# STM32_microcontroller_RF.net
KiCad netlist of a schematic drawn in Altium Designer
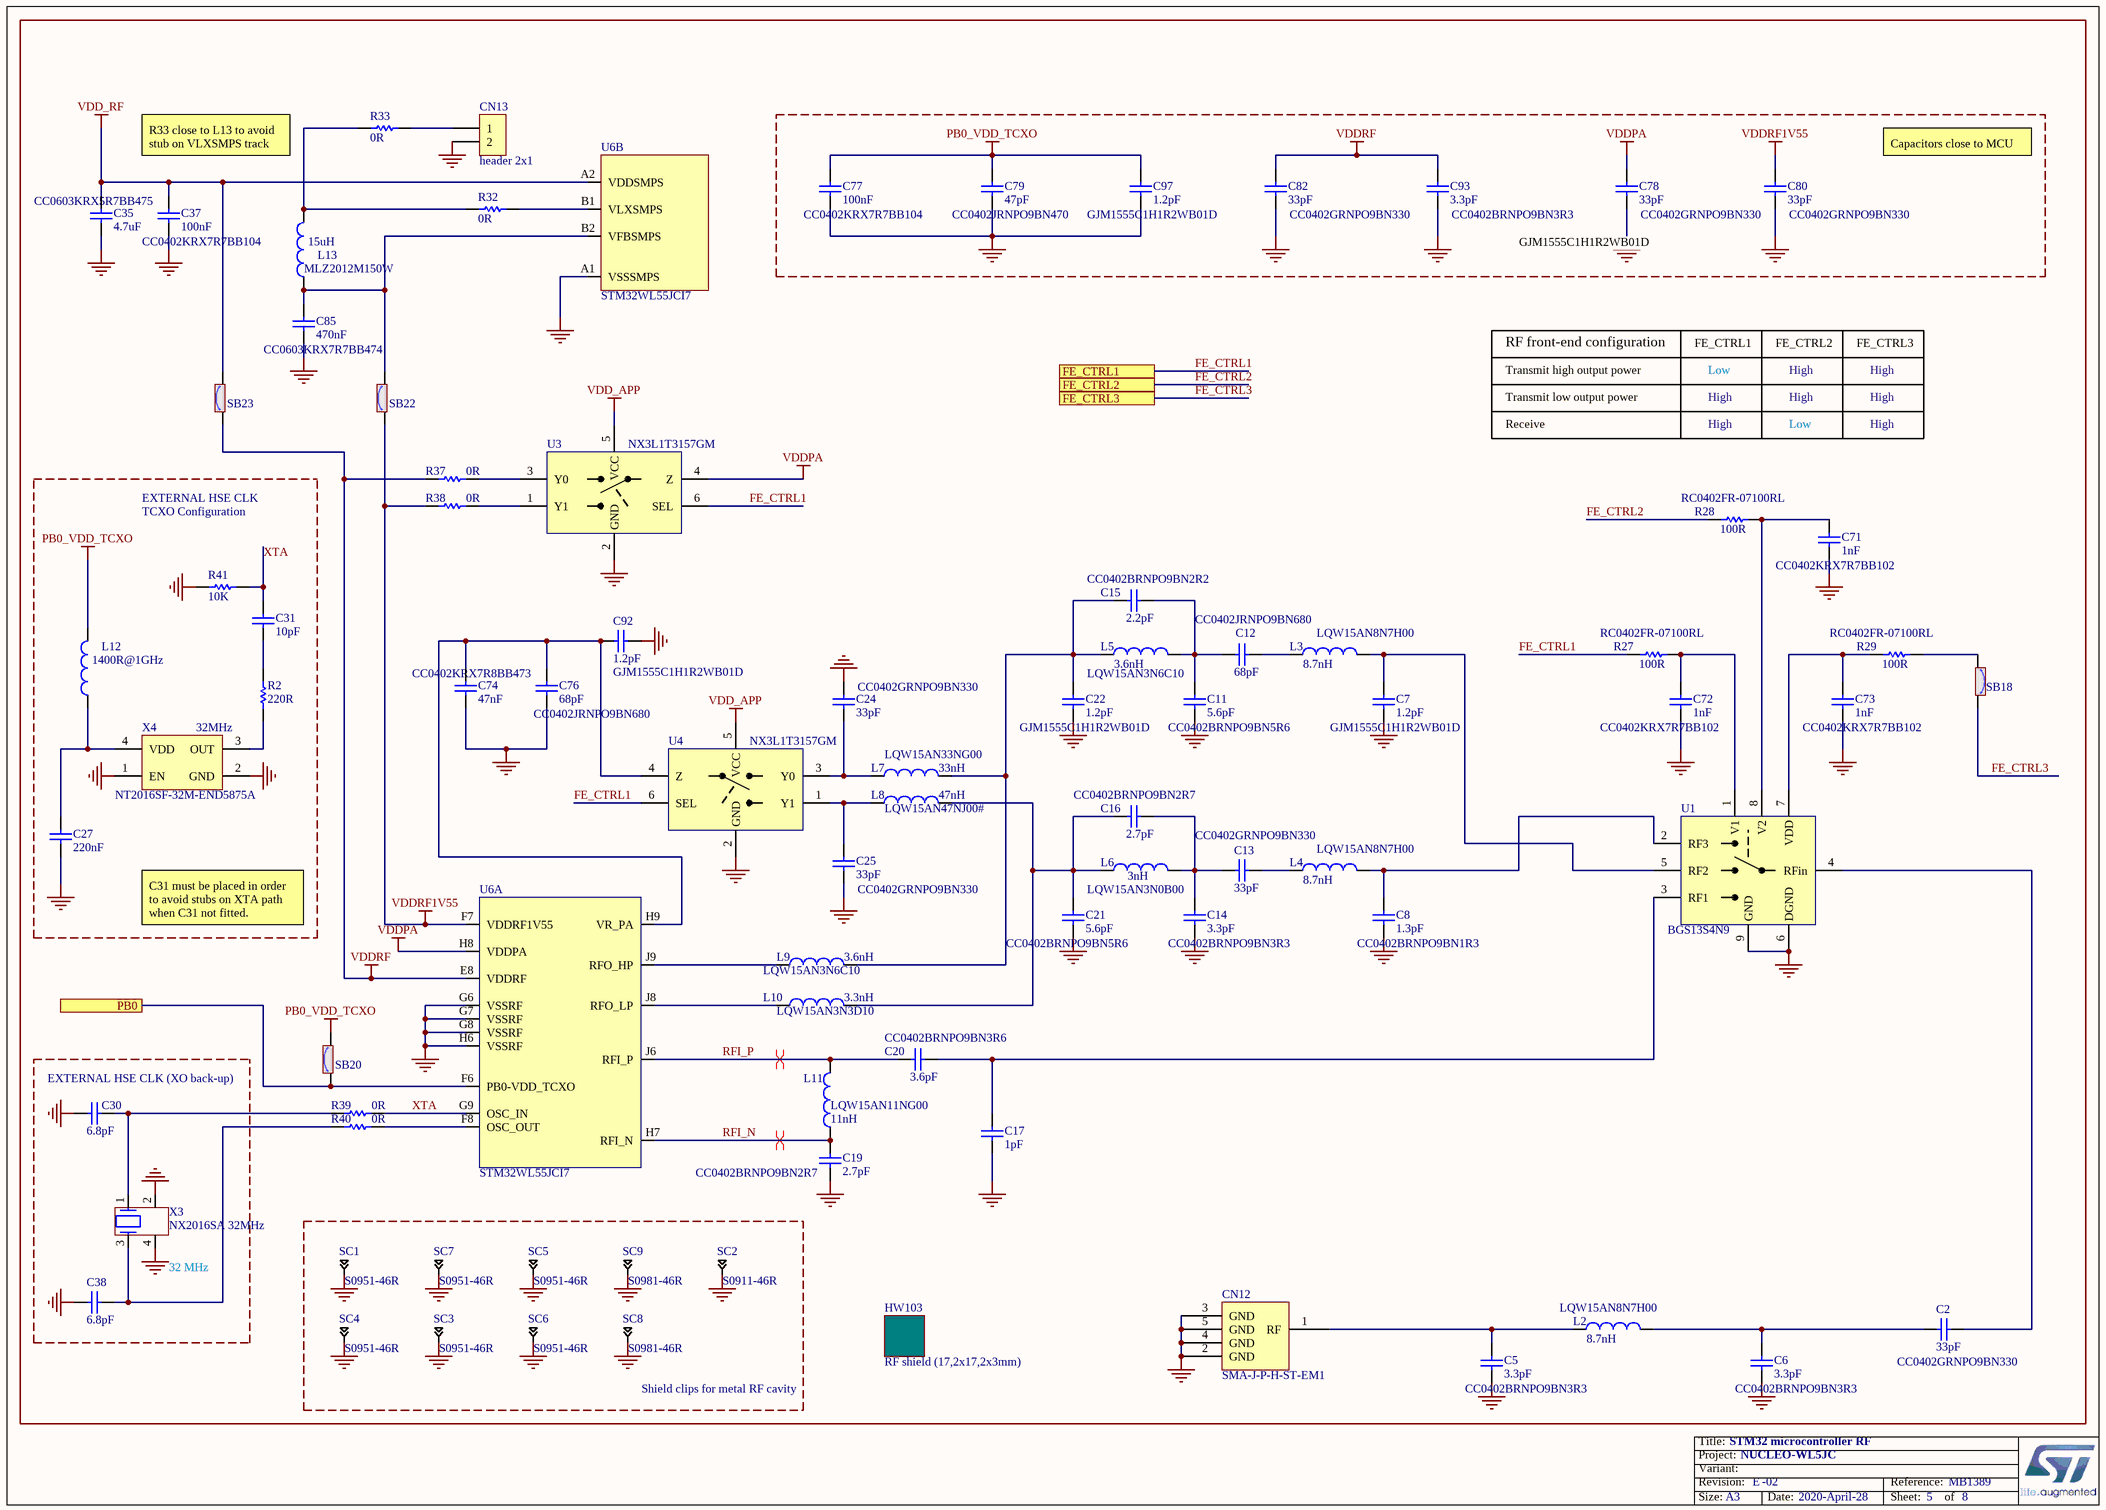
[diagram p0: STM32_microcontroller_RF.SchDoc]

(export (version "E")
  (design (tool "Eeschema 10.0.6"))
  (components
    (comp (ref "C2")
      (value "33pF")
      (footprint "C0402")
      (description "Capacitor, MLCC, 33pF, 50V, NPO, +/-2%, 0402, T=0,5mm")
      (fields
        (field (name "INTERNAL_PART_NUMBER") "MCD-01784")
        (field (name "MANUFACTURER_PART_NUMBER") "CC0402GRNPO9BN330")
        (field (name "MANUFACTURER") "YAGEO")
        (field (name "PROVIDED_BY") "SUBCO")
      )
      (libsource (lib "MCD_PARTS_database") (part "Capacitor"))
    )
    (comp (ref "C5")
      (value "3.3pF")
      (footprint "C0402")
      (description "Capacitor, MLCC, 3.3pF, 50V, NPO, +/-0.1pF, 0402, T=0,5mm")
      (fields
        (field (name "INTERNAL_PART_NUMBER") "MCD-01775")
        (field (name "MANUFACTURER_PART_NUMBER") "CC0402BRNPO9BN3R3")
        (field (name "MANUFACTURER") "YAGEO")
        (field (name "PROVIDED_BY") "SUBCO")
      )
      (libsource (lib "MCD_PARTS_database") (part "Capacitor"))
    )
    (comp (ref "C6")
      (value "3.3pF")
      (footprint "C0402")
      (description "Capacitor, MLCC, 3.3pF, 50V, NPO, +/-0.1pF, 0402, T=0,5mm")
      (fields
        (field (name "INTERNAL_PART_NUMBER") "MCD-01775")
        (field (name "MANUFACTURER_PART_NUMBER") "CC0402BRNPO9BN3R3")
        (field (name "MANUFACTURER") "YAGEO")
        (field (name "PROVIDED_BY") "SUBCO")
      )
      (libsource (lib "MCD_PARTS_database") (part "Capacitor"))
    )
    (comp (ref "C7")
      (value "1.2pF")
      (footprint "C0402")
      (description "Capacitor, High Q type for high frequency and high power, SMD, 1.2pF, 50V, 0,05pf, 0402")
      (fields
        (field (name "INTERNAL_PART_NUMBER") "MCD-02065")
        (field (name "MANUFACTURER") "MURATA")
        (field (name "MANUFACTURER_PART_NUMBER") "GJM1555C1H1R2WB01D")
      )
      (libsource (lib "MCD_PARTS_database") (part "Capacitor"))
    )
    (comp (ref "C8")
      (value "1.3pF")
      (footprint "C0402")
      (description "Capacitor, MLCC, 1.3pF, 50V, NPO, +/-0.1pF, 0402, T=0,5mm")
      (fields
        (field (name "INTERNAL_PART_NUMBER") "MCD-01772")
        (field (name "MANUFACTURER_PART_NUMBER") "CC0402BRNPO9BN1R3")
        (field (name "MANUFACTURER") "YAGEO")
        (field (name "PROVIDED_BY") "SUBCO")
      )
      (libsource (lib "MCD_PARTS_database") (part "Capacitor"))
    )
    (comp (ref "C11")
      (value "5.6pF")
      (footprint "C0402")
      (description "Capacitor, MLCC, 5.6pF, 50V, NPO, +/- 0.1pF, 0402, T=0,5mm")
      (fields
        (field (name "INTERNAL_PART_NUMBER") "MCD-01374")
        (field (name "MANUFACTURER") "YAGEO")
        (field (name "MANUFACTURER_PART_NUMBER") "CC0402BRNPO9BN5R6")
      )
      (libsource (lib "MCD_PARTS_database") (part "Capacitor"))
    )
    (comp (ref "C12")
      (value "68pF")
      (footprint "C0402")
      (description "Capacitor, MLCC, 68pF, 50V, NPO, +/-5%, 0402, T=0,5mm")
      (fields
        (field (name "INTERNAL_PART_NUMBER") "MCD-01604")
        (field (name "MANUFACTURER") "YAGEO")
        (field (name "MANUFACTURER_PART_NUMBER") "CC0402JRNPO9BN680")
      )
      (libsource (lib "MCD_PARTS_database") (part "Capacitor"))
    )
    (comp (ref "C13")
      (value "33pF")
      (footprint "C0402")
      (description "Capacitor, MLCC, 33pF, 50V, NPO, +/-2%, 0402, T=0,5mm")
      (fields
        (field (name "INTERNAL_PART_NUMBER") "MCD-01784")
        (field (name "MANUFACTURER_PART_NUMBER") "CC0402GRNPO9BN330")
        (field (name "MANUFACTURER") "YAGEO")
        (field (name "PROVIDED_BY") "SUBCO")
      )
      (libsource (lib "MCD_PARTS_database") (part "Capacitor"))
    )
    (comp (ref "C14")
      (value "3.3pF")
      (footprint "C0402")
      (description "Capacitor, MLCC, 3.3pF, 50V, NPO, +/-0.1pF, 0402, T=0,5mm")
      (fields
        (field (name "INTERNAL_PART_NUMBER") "MCD-01775")
        (field (name "MANUFACTURER_PART_NUMBER") "CC0402BRNPO9BN3R3")
        (field (name "MANUFACTURER") "YAGEO")
        (field (name "PROVIDED_BY") "SUBCO")
      )
      (libsource (lib "MCD_PARTS_database") (part "Capacitor"))
    )
    (comp (ref "C15")
      (value "2.2pF")
      (footprint "C0402")
      (description "Capacitor, MLCC, 2.2pF, 50V, NPO, +/-0.1pF, 0402, T=0,5mm")
      (fields
        (field (name "INTERNAL_PART_NUMBER") "MCD-01773")
        (field (name "MANUFACTURER") "YAGEO")
        (field (name "MANUFACTURER_PART_NUMBER") "CC0402BRNPO9BN2R2")
      )
      (libsource (lib "MCD_PARTS_database") (part "Capacitor"))
    )
    (comp (ref "C16")
      (value "2.7pF")
      (footprint "C0402")
      (description "Capacitor, MLCC, 2.7pF, 50V, NPO, +/-0.1pF, 0402, T=0,5mm")
      (fields
        (field (name "INTERNAL_PART_NUMBER") "MCD-01774")
        (field (name "MANUFACTURER_PART_NUMBER") "CC0402BRNPO9BN2R7")
        (field (name "MANUFACTURER") "YAGEO")
        (field (name "PROVIDED_BY") "SUBCO")
      )
      (libsource (lib "MCD_PARTS_database") (part "Capacitor"))
    )
    (comp (ref "C17")
      (value "1pF")
      (footprint "C0402")
      (description "Capacitor, MLCC, 1pF, 50V, NPO, +/-0.1pF, 0402, T=0,5mm")
      (fields (field (name "INTERNAL_PART_NUMBER") "MCD-01600") (field (name "MANUFACTURER") "YAGEO"))
      (libsource (lib "MCD_PARTS_database") (part "Capacitor"))
    )
    (comp (ref "C19")
      (value "2.7pF")
      (footprint "C0402")
      (description "Capacitor, MLCC, 2.7pF, 50V, NPO, +/-0.1pF, 0402, T=0,5mm")
      (fields
        (field (name "INTERNAL_PART_NUMBER") "MCD-01774")
        (field (name "MANUFACTURER_PART_NUMBER") "CC0402BRNPO9BN2R7")
        (field (name "MANUFACTURER") "YAGEO")
        (field (name "PROVIDED_BY") "SUBCO")
      )
      (libsource (lib "MCD_PARTS_database") (part "Capacitor"))
    )
    (comp (ref "C20")
      (value "3.6pF")
      (footprint "C0402")
      (description "Capacitor, MLCC, 3.6pF, 50V, NPO, +/-0.1pF, 0402, T=0,5mm")
      (fields
        (field (name "INTERNAL_PART_NUMBER") "MCD-01776")
        (field (name "MANUFACTURER_PART_NUMBER") "CC0402BRNPO9BN3R6")
        (field (name "MANUFACTURER") "YAGEO")
        (field (name "PROVIDED_BY") "SUBCO")
      )
      (libsource (lib "MCD_PARTS_database") (part "Capacitor"))
    )
    (comp (ref "C21")
      (value "5.6pF")
      (footprint "C0402")
      (description "Capacitor, MLCC, 5.6pF, 50V, NPO, +/- 0.1pF, 0402, T=0,5mm")
      (fields
        (field (name "INTERNAL_PART_NUMBER") "MCD-01374")
        (field (name "MANUFACTURER_PART_NUMBER") "CC0402BRNPO9BN5R6")
        (field (name "MANUFACTURER") "YAGEO")
        (field (name "PROVIDED_BY") "SUBCO")
      )
      (libsource (lib "MCD_PARTS_database") (part "Capacitor"))
    )
    (comp (ref "C22")
      (value "1.2pF")
      (footprint "C0402")
      (description "Capacitor, High Q type for high frequency and high power, SMD, 1.2pF, 50V, 0,05pf, 0402")
      (fields
        (field (name "INTERNAL_PART_NUMBER") "MCD-02065")
        (field (name "MANUFACTURER") "MURATA")
        (field (name "MANUFACTURER_PART_NUMBER") "GJM1555C1H1R2WB01D")
      )
      (libsource (lib "MCD_PARTS_database") (part "Capacitor"))
    )
    (comp (ref "C24")
      (value "33pF")
      (footprint "C0402")
      (description "Capacitor, MLCC, 33pF, 50V, NPO, +/-2%, 0402, T=0,5mm")
      (fields
        (field (name "INTERNAL_PART_NUMBER") "MCD-01784")
        (field (name "MANUFACTURER_PART_NUMBER") "CC0402GRNPO9BN330")
        (field (name "MANUFACTURER") "YAGEO")
        (field (name "PROVIDED_BY") "SUBCO")
      )
      (libsource (lib "MCD_PARTS_database") (part "Capacitor"))
    )
    (comp (ref "C25")
      (value "33pF")
      (footprint "C0402")
      (description "Capacitor, MLCC, 33pF, 50V, NPO, +/-2%, 0402, T=0,5mm")
      (fields
        (field (name "INTERNAL_PART_NUMBER") "MCD-01784")
        (field (name "MANUFACTURER_PART_NUMBER") "CC0402GRNPO9BN330")
        (field (name "MANUFACTURER") "YAGEO")
        (field (name "PROVIDED_BY") "SUBCO")
      )
      (libsource (lib "MCD_PARTS_database") (part "Capacitor"))
    )
    (comp (ref "C27")
      (value "220nF")
      (footprint "C0402")
      (description "Capacitor, MLCC, 220nF, 16V, X7R, +/-10%, ,0402, T=0,5mm")
      (fields (field (name "INTERNAL_PART_NUMBER") "MCD-00602") (field (name "MANUFACTURER") "TDK"))
      (libsource (lib "MCD_PARTS_database") (part "Capacitor"))
    )
    (comp (ref "C30")
      (value "6.8pF")
      (footprint "C0402")
      (description "Capacitor, MLCC, 6.8pF, 50V, NPO, +-0.25pF, 0402, T=0.5mm")
      (fields
        (field (name "INTERNAL_PART_NUMBER") "MCD-00674")
        (field (name "MANUFACTURER_PART_NUMBER") "CC0402CRNPO9BN6R8")
        (field (name "PROVIDED_BY") "SUBCO")
      )
      (libsource (lib "MCD_PARTS_database") (part "Capacitor"))
    )
    (comp (ref "C31")
      (value "10pF")
      (footprint "C0402")
      (description "Capacitor, MLCC, 10pF, 50V, NPO, +/-5%, 0402, T=0,5mm")
      (fields (field (name "INTERNAL_PART_NUMBER") "MCD-00015") (field (name "MANUFACTURER") "YAGEO"))
      (libsource (lib "MCD_PARTS_database") (part "Capacitor"))
    )
    (comp (ref "C35")
      (value "4.7uF")
      (footprint "C0603")
      (description "Capacitor, MLCC, 4.7uF, 16V, X5R, 10%, 0603, T=0.8mm")
      (fields
        (field (name "INTERNAL_PART_NUMBER") "MCD-00009")
        (field (name "MANUFACTURER_PART_NUMBER") "CC0603KRX5R7BB475")
        (field (name "MANUFACTURER") "YAGEO")
        (field (name "PROVIDED_BY") "SUBCO")
      )
      (libsource (lib "MCD_PARTS_database") (part "Capacitor"))
    )
    (comp (ref "C37")
      (value "100nF")
      (footprint "C0402")
      (description "Capacitor, MLCC, 100nF, 16V, X7R, 10%, 0402, T=0,5mm")
      (fields
        (field (name "INTERNAL_PART_NUMBER") "MCD-00102")
        (field (name "MANUFACTURER_PART_NUMBER") "CC0402KRX7R7BB104")
        (field (name "MANUFACTURER") "YAGEO")
        (field (name "PROVIDED_BY") "SUBCO")
      )
      (libsource (lib "MCD_PARTS_database") (part "Capacitor"))
    )
    (comp (ref "C38")
      (value "6.8pF")
      (footprint "C0402")
      (description "Capacitor, MLCC, 6.8pF, 50V, NPO, +-0.25pF, 0402, T=0.5mm")
      (fields
        (field (name "INTERNAL_PART_NUMBER") "MCD-00674")
        (field (name "MANUFACTURER_PART_NUMBER") "CC0402CRNPO9BN6R8")
        (field (name "PROVIDED_BY") "SUBCO")
      )
      (libsource (lib "MCD_PARTS_database") (part "Capacitor"))
    )
    (comp (ref "C71")
      (value "1nF")
      (footprint "C0402")
      (description "Capacitor, MLCC, 1nF, 16V, X7R, 10%, 0402, T=0.5mm")
      (fields
        (field (name "INTERNAL_PART_NUMBER") "MCD-00198")
        (field (name "MANUFACTURER_PART_NUMBER") "CC0402KRX7R7BB102")
        (field (name "MANUFACTURER") "YAGEO")
        (field (name "PROVIDED_BY") "SUBCO")
      )
      (libsource (lib "MCD_PARTS_database") (part "Capacitor"))
    )
    (comp (ref "C72")
      (value "1nF")
      (footprint "C0402")
      (description "Capacitor, MLCC, 1nF, 16V, X7R, 10%, 0402, T=0.5mm")
      (fields
        (field (name "INTERNAL_PART_NUMBER") "MCD-00198")
        (field (name "MANUFACTURER_PART_NUMBER") "CC0402KRX7R7BB102")
        (field (name "MANUFACTURER") "YAGEO")
        (field (name "PROVIDED_BY") "SUBCO")
      )
      (libsource (lib "MCD_PARTS_database") (part "Capacitor"))
    )
    (comp (ref "C73")
      (value "1nF")
      (footprint "C0402")
      (description "Capacitor, MLCC, 1nF, 16V, X7R, 10%, 0402, T=0.5mm")
      (fields
        (field (name "INTERNAL_PART_NUMBER") "MCD-00198")
        (field (name "MANUFACTURER_PART_NUMBER") "CC0402KRX7R7BB102")
        (field (name "MANUFACTURER") "YAGEO")
        (field (name "PROVIDED_BY") "SUBCO")
      )
      (libsource (lib "MCD_PARTS_database") (part "Capacitor"))
    )
    (comp (ref "C74")
      (value "47nF")
      (footprint "C0402")
      (description "Capacitor, MLCC, 47nF, 25V, X7R, +-10%, 0402, T=0,5mm")
      (fields
        (field (name "INTERNAL_PART_NUMBER") "MCD-01605")
        (field (name "MANUFACTURER_PART_NUMBER") "CC0402KRX7R8BB473")
        (field (name "MANUFACTURER") "YAGEO")
        (field (name "PROVIDED_BY") "SUBCO")
      )
      (libsource (lib "MCD_PARTS_database") (part "Capacitor"))
    )
    (comp (ref "C76")
      (value "68pF")
      (footprint "C0402")
      (description "Capacitor, MLCC, 68pF, 50V, NPO, +-5%, 0402, T=0,5mm")
      (fields
        (field (name "INTERNAL_PART_NUMBER") "MCD-01604")
        (field (name "MANUFACTURER_PART_NUMBER") "CC0402JRNPO9BN680")
        (field (name "MANUFACTURER") "YAGEO")
        (field (name "PROVIDED_BY") "SUBCO")
      )
      (libsource (lib "MCD_PARTS_database") (part "Capacitor"))
    )
    (comp (ref "C77")
      (value "100nF")
      (footprint "C0402")
      (description "Capacitor, MLCC, 100nF, 16V, X7R, 10%, 0402, T=0,5mm")
      (fields
        (field (name "INTERNAL_PART_NUMBER") "MCD-00102")
        (field (name "MANUFACTURER_PART_NUMBER") "CC0402KRX7R7BB104")
        (field (name "MANUFACTURER") "YAGEO")
        (field (name "PROVIDED_BY") "SUBCO")
      )
      (libsource (lib "MCD_PARTS_database") (part "Capacitor"))
    )
    (comp (ref "C78")
      (value "33pF")
      (footprint "C0402")
      (description "Capacitor, MLCC, 33pF, 50V, NPO, +/-2%, 0402, T=0,5mm")
      (fields
        (field (name "INTERNAL_PART_NUMBER") "MCD-01784")
        (field (name "MANUFACTURER_PART_NUMBER") "CC0402GRNPO9BN330")
        (field (name "MANUFACTURER") "YAGEO")
        (field (name "PROVIDED_BY") "SUBCO")
      )
      (libsource (lib "MCD_PARTS_database") (part "Capacitor"))
    )
    (comp (ref "C79")
      (value "47pF")
      (footprint "C0402")
      (description "Capacitor, MLCC, 147pF, 50V, NPO, +-5%, 0402, T=0,5mm")
      (fields
        (field (name "INTERNAL_PART_NUMBER") "MCD-01603")
        (field (name "MANUFACTURER_PART_NUMBER") "CC0402JRNPO9BN470")
        (field (name "MANUFACTURER") "YAGEO")
        (field (name "PROVIDED_BY") "SUBCO")
      )
      (libsource (lib "MCD_PARTS_database") (part "Capacitor"))
    )
    (comp (ref "C80")
      (value "33pF")
      (footprint "C0402")
      (description "Capacitor, MLCC, 33pF, 50V, NPO, +/-2%, 0402, T=0,5mm")
      (fields
        (field (name "INTERNAL_PART_NUMBER") "MCD-01784")
        (field (name "MANUFACTURER_PART_NUMBER") "CC0402GRNPO9BN330")
        (field (name "MANUFACTURER") "YAGEO")
        (field (name "PROVIDED_BY") "SUBCO")
      )
      (libsource (lib "MCD_PARTS_database") (part "Capacitor"))
    )
    (comp (ref "C82")
      (value "33pF")
      (footprint "C0402")
      (description "Capacitor, MLCC, 33pF, 50V, NPO, +/-2%, 0402, T=0,5mm")
      (fields
        (field (name "INTERNAL_PART_NUMBER") "MCD-01784")
        (field (name "MANUFACTURER_PART_NUMBER") "CC0402GRNPO9BN330")
        (field (name "MANUFACTURER") "YAGEO")
        (field (name "PROVIDED_BY") "SUBCO")
      )
      (libsource (lib "MCD_PARTS_database") (part "Capacitor"))
    )
    (comp (ref "C85")
      (value "470nF")
      (footprint "C0603")
      (description "Capacitor, MLCC, 470nF, 16V, X7R, 10%, 0603, T=0.8mm")
      (fields
        (field (name "INTERNAL_PART_NUMBER") "MCD-01006")
        (field (name "MANUFACTURER_PART_NUMBER") "CC0603KRX7R7BB474")
        (field (name "MANUFACTURER") "YAGEO")
        (field (name "PROVIDED_BY") "SUBCO")
      )
      (libsource (lib "MCD_PARTS_database") (part "Capacitor"))
    )
    (comp (ref "C92")
      (value "1.2pF")
      (footprint "C0402")
      (description "Capacitor, High Q type for high frequency and high power, SMD, 1.2pF, 50V, 0,05pf, 0402")
      (fields
        (field (name "INTERNAL_PART_NUMBER") "MCD-02065")
        (field (name "MANUFACTURER") "MURATA")
        (field (name "MANUFACTURER_PART_NUMBER") "GJM1555C1H1R2WB01D")
      )
      (libsource (lib "MCD_PARTS_database") (part "Capacitor"))
    )
    (comp (ref "C93")
      (value "3.3pF")
      (footprint "C0402")
      (description "Capacitor, MLCC, 3.3pF, 50V, NPO, +/-0.1pF, 0402, T=0,5mm")
      (fields
        (field (name "INTERNAL_PART_NUMBER") "MCD-01775")
        (field (name "MANUFACTURER") "YAGEO")
        (field (name "MANUFACTURER_PART_NUMBER") "CC0402BRNPO9BN3R3")
      )
      (libsource (lib "MCD_PARTS_database") (part "Capacitor"))
    )
    (comp (ref "C97")
      (value "1.2pF")
      (footprint "C0402")
      (description "Capacitor, High Q type for high frequency and high power, SMD, 1.2pF, 50V, 0,05pf, 0402")
      (fields
        (field (name "INTERNAL_PART_NUMBER") "MCD-02065")
        (field (name "MANUFACTURER") "MURATA")
        (field (name "MANUFACTURER_PART_NUMBER") "GJM1555C1H1R2WB01D")
      )
      (libsource (lib "MCD_PARTS_database") (part "Capacitor"))
    )
    (comp (ref "CN12")
      (value "SMA-J-P-H-ST-EM1")
      (footprint "CON_SAMTEC_SMA-J-P-X-ST-EM1")
      (description "RF SMA connector PCB edge")
      (fields
        (field (name "INTERNAL_PART_NUMBER") "MCD-00279")
        (field (name "MANUFACTURER") "SAMTEC")
        (field (name "PROVIDED_BY") "SUBCO")
      )
      (libsource (lib "MCD_PARTS_database") (part "SMA-J-P-H-ST-EM1"))
    )
    (comp (ref "CN13")
      (value "header 2x1")
      (footprint "CON_988-JIUBABA_PHFS25-11-02-G0B115-T-1")
      (description "Header, 2x1, 2.54mm, VR, TH, Height 6mm/3mm")
      (fields
        (field (name "INTERNAL_PART_NUMBER") "MCD-00314")
        (field (name "MANUFACTURER_PART_NUMBER") "PHFS25-11-02-G0B115-T-1")
        (field (name "PROVIDED_BY") "SUBCO")
      )
      (libsource (lib "MCD_PARTS_database") (part "Header 2x1"))
    )
    (comp (ref "HW103")
      (value "RF shield (17,2x17,2x3mm)")
      (footprint "SHIELD_RF_ST-CUSTOM_17P2X17P2_H3")
      (description "RF shield (17,2x17,2x3mm), Brass with Sn finishing, Sheet tickness : 0,2mm")
      (fields (field (name "INTERNAL_PART_NUMBER") "MCD-02088") (field (name "BMS_PART_NUMBER") "TBD"))
      (libsource (lib "MCD_PARTS_database") (part "Daughter_Board"))
    )
    (comp (ref "L2")
      (value "8.7nH")
      (footprint "IND_0402_MURATA_LQW15AN_H0P5")
      (description "0402 inductor, 8.7nH +/-3%, 540mA max, 0.14 ohm DC max, Q min = 25")
      (fields
        (field (name "INTERNAL_PART_NUMBER") "MCD-01768")
        (field (name "MANUFACTURER_PART_NUMBER") "LQW15AN8N7H00")
        (field (name "MANUFACTURER") "MURATA")
        (field (name "PROVIDED_BY") "SUBCO")
      )
      (libsource (lib "MCD_PARTS_database") (part "Inductor"))
    )
    (comp (ref "L3")
      (value "8.7nH")
      (footprint "IND_0402_MURATA_LQW15AN_H0P5")
      (description "0402 inductor, 8.7nH +/-3%, 540mA max, 0.14 ohm DC max, Q min = 25")
      (fields
        (field (name "INTERNAL_PART_NUMBER") "MCD-01768")
        (field (name "MANUFACTURER") "MURATA")
        (field (name "MANUFACTURER_PART_NUMBER") "LQW15AN8N7H00")
      )
      (libsource (lib "MCD_PARTS_database") (part "Inductor"))
    )
    (comp (ref "L4")
      (value "8.7nH")
      (footprint "IND_0402_MURATA_LQW15AN_H0P5")
      (description "0402 inductor, 8.7nH +/-3%, 540mA max, 0.14 ohm DC max, Q min = 25")
      (fields
        (field (name "INTERNAL_PART_NUMBER") "MCD-01768")
        (field (name "MANUFACTURER_PART_NUMBER") "LQW15AN8N7H00")
        (field (name "MANUFACTURER") "MURATA")
        (field (name "PROVIDED_BY") "SUBCO")
      )
      (libsource (lib "MCD_PARTS_database") (part "Inductor"))
    )
    (comp (ref "L5")
      (value "3.6nH")
      (footprint "IND_0402_MURATA_LQW15AN_H0P5")
      (description "0402 inductor, 3.6nH +/-0.2nH, 900mA max, 0.04 ohm DC max, Q min = 30")
      (fields
        (field (name "INTERNAL_PART_NUMBER") "MCD-01762")
        (field (name "MANUFACTURER") "MURATA")
        (field (name "MANUFACTURER_PART_NUMBER") "LQW15AN3N6C10")
      )
      (libsource (lib "MCD_PARTS_database") (part "Inductor"))
    )
    (comp (ref "L6")
      (value "3nH")
      (footprint "IND_0402_MURATA_LQW15AN_H0P5")
      (description "0402 inductor, 3nH +-0.1nH, 750mA max, 0.07 ohm DC max, Q min = 20")
      (fields
        (field (name "INTERNAL_PART_NUMBER") "MCD-01922")
        (field (name "MANUFACTURER_PART_NUMBER") "LQW15AN3N0B00")
        (field (name "MANUFACTURER") "MURATA")
        (field (name "PROVIDED_BY") "SUBCO")
      )
      (libsource (lib "MCD_PARTS_database") (part "Inductor"))
    )
    (comp (ref "L7")
      (value "33nH")
      (footprint "IND_0402_MURATA_LQW15AN_H0P5")
      (description "Inductor, 33nH +/-2%, 260mA max , 0.63 ohm DC max, 0402, Q min = 25.")
      (fields
        (field (name "INTERNAL_PART_NUMBER") "MCD-02069")
        (field (name "MANUFACTURER") "MURATA")
        (field (name "MANUFACTURER_PART_NUMBER") "LQW15AN33NG00")
      )
      (libsource (lib "MCD_PARTS_database") (part "Inductor"))
    )
    (comp (ref "L8")
      (value "47nH")
      (footprint "IND_0402_MURATA_LQW15AN2N4C00X")
      (description "Inductor, 47nH, +-5%, 210mA, 1.08ohm DC max, 0402")
      (fields
        (field (name "INTERNAL_PART_NUMBER") "MCD-01609")
        (field (name "MANUFACTURER_PART_NUMBER") "LQW15AN47NJ00#")
        (field (name "MANUFACTURER") "MURATA")
        (field (name "PROVIDED_BY") "SUBCO")
      )
      (libsource (lib "MCD_PARTS_database") (part "Inductor"))
    )
    (comp (ref "L9")
      (value "3.6nH")
      (footprint "IND_0402_MURATA_LQW15AN_H0P5")
      (description "0402 inductor, 3.6nH +/-0.2nH, 900mA max, 0.04 ohm DC max, Q min = 30")
      (fields
        (field (name "INTERNAL_PART_NUMBER") "MCD-01762")
        (field (name "MANUFACTURER_PART_NUMBER") "LQW15AN3N6C10")
        (field (name "MANUFACTURER") "MURATA")
        (field (name "PROVIDED_BY") "SUBCO")
      )
      (libsource (lib "MCD_PARTS_database") (part "Inductor"))
    )
    (comp (ref "L10")
      (value "3.3nH")
      (footprint "IND_0402_MURATA_LQW15AN_H0P5")
      (description "0402 inductor, 3.3nH +-0.5nH, 900mA max, 0.04 ohm DC max, Q min = 30")
      (fields
        (field (name "INTERNAL_PART_NUMBER") "MCD-01761")
        (field (name "MANUFACTURER_PART_NUMBER") "LQW15AN3N3D10")
        (field (name "MANUFACTURER") "MURATA")
        (field (name "PROVIDED_BY") "SUBCO")
      )
      (libsource (lib "MCD_PARTS_database") (part "Inductor"))
    )
    (comp (ref "L11")
      (value "11nH")
      (footprint "IND_0402_MURATA_LQW15AN_H0P5")
      (description "0402 inductor, 11nH +-2%, 500mA max, 0.14 ohm DC max, Q min = 30")
      (fields
        (field (name "INTERNAL_PART_NUMBER") "MCD-01921")
        (field (name "MANUFACTURER_PART_NUMBER") "LQW15AN11NG00")
        (field (name "MANUFACTURER") "MURATA")
        (field (name "PROVIDED_BY") "SUBCO")
      )
      (libsource (lib "MCD_PARTS_database") (part "Inductor"))
    )
    (comp (ref "L12")
      (value "1400R@1GHz")
      (footprint "IND_0402_MURATA_BLM15H_H0P5")
      (description "ferrite bead, 1400ohms at 1GHz, 250mA, 1.1ohms DC max")
      (fields
        (field (name "INTERNAL_PART_NUMBER") "MCD-01610")
        (field (name "MANUFACTURER_PART_NUMBER") "BLM15HG102SN1#")
        (field (name "PROVIDED_BY") "SUBCO")
      )
      (libsource (lib "MCD_PARTS_database") (part "Inductor"))
    )
    (comp (ref "L13")
      (value "15uH")
      (footprint "IND_TDK_MLZ2012M150W")
      (description "MLZ2012 Multilayer Shielded Inductor 15uH, +/-5%")
      (fields
        (field (name "INTERNAL_PART_NUMBER") "MCD-01433")
        (field (name "MANUFACTURER_PART_NUMBER") "MLZ2012M150W")
        (field (name "MANUFACTURER") "TDK")
        (field (name "PROVIDED_BY") "SUBCO")
      )
      (libsource (lib "MCD_PARTS_database") (part "Inductor"))
    )
    (comp (ref "R2")
      (value "220R")
      (footprint "R0402")
      (description "Resistor,220R,0402,1%,1/16W")
      (fields
        (field (name "INTERNAL_PART_NUMBER") "MCD-00427")
        (field (name "MANUFACTURER_PART_NUMBER") "RC0402FR-07220RL")
        (field (name "PROVIDED_BY") "SUBCO")
      )
      (libsource (lib "MCD_PARTS_database") (part "Resistor"))
    )
    (comp (ref "R27")
      (value "100R")
      (footprint "R0402")
      (description "Resistor,100R,0402,1%,1/16W")
      (fields
        (field (name "INTERNAL_PART_NUMBER") "MCD-00119")
        (field (name "MANUFACTURER_PART_NUMBER") "RC0402FR-07100RL")
        (field (name "MANUFACTURER") "YAGEO")
        (field (name "PROVIDED_BY") "SUBCO")
      )
      (libsource (lib "MCD_PARTS_database") (part "Resistor"))
    )
    (comp (ref "R28")
      (value "100R")
      (footprint "R0402")
      (description "Resistor,100R,0402,1%,1/16W")
      (fields
        (field (name "INTERNAL_PART_NUMBER") "MCD-00119")
        (field (name "MANUFACTURER_PART_NUMBER") "RC0402FR-07100RL")
        (field (name "MANUFACTURER") "YAGEO")
        (field (name "PROVIDED_BY") "SUBCO")
      )
      (libsource (lib "MCD_PARTS_database") (part "Resistor"))
    )
    (comp (ref "R29")
      (value "100R")
      (footprint "R0402")
      (description "Resistor,100R,0402,1%,1/16W")
      (fields
        (field (name "INTERNAL_PART_NUMBER") "MCD-00119")
        (field (name "MANUFACTURER_PART_NUMBER") "RC0402FR-07100RL")
        (field (name "MANUFACTURER") "YAGEO")
        (field (name "PROVIDED_BY") "SUBCO")
      )
      (libsource (lib "MCD_PARTS_database") (part "Resistor"))
    )
    (comp (ref "R32")
      (value "0R")
      (footprint "R0402")
      (description "Resistor,0R,0402,5%,1/16W")
      (fields
        (field (name "INTERNAL_PART_NUMBER") "MCD-00052")
        (field (name "MANUFACTURER_PART_NUMBER") "RC0402JR-070RL")
        (field (name "PROVIDED_BY") "SUBCO")
      )
      (libsource (lib "MCD_PARTS_database") (part "Resistor"))
    )
    (comp (ref "R33")
      (value "0R")
      (footprint "R0402")
      (description "Resistor,0R,0402,5%,1/16W")
      (fields
        (field (name "INTERNAL_PART_NUMBER") "MCD-00052")
        (field (name "MANUFACTURER_PART_NUMBER") "RC0402JR-070RL")
        (field (name "PROVIDED_BY") "SUBCO")
      )
      (libsource (lib "MCD_PARTS_database") (part "Resistor"))
    )
    (comp (ref "R37")
      (value "0R")
      (footprint "R0402")
      (description "Resistor,0R,0402,5%,1/16W")
      (fields
        (field (name "INTERNAL_PART_NUMBER") "MCD-00052")
        (field (name "MANUFACTURER_PART_NUMBER") "RC0402JR-070RL")
        (field (name "PROVIDED_BY") "SUBCO")
      )
      (libsource (lib "MCD_PARTS_database") (part "Resistor"))
    )
    (comp (ref "R38")
      (value "0R")
      (footprint "R0402")
      (description "Resistor,0R,0402,5%,1/16W")
      (fields
        (field (name "INTERNAL_PART_NUMBER") "MCD-00052")
        (field (name "MANUFACTURER_PART_NUMBER") "RC0402JR-070RL")
        (field (name "PROVIDED_BY") "SUBCO")
      )
      (libsource (lib "MCD_PARTS_database") (part "Resistor"))
    )
    (comp (ref "R39")
      (value "0R")
      (footprint "R0402")
      (description "Resistor,0R,0402,5%,1/16W")
      (fields
        (field (name "INTERNAL_PART_NUMBER") "MCD-00052")
        (field (name "MANUFACTURER_PART_NUMBER") "RC0402JR-070RL")
        (field (name "PROVIDED_BY") "SUBCO")
      )
      (libsource (lib "MCD_PARTS_database") (part "Resistor"))
    )
    (comp (ref "R40")
      (value "0R")
      (footprint "R0402")
      (description "Resistor,0R,0402,5%,1/16W")
      (fields
        (field (name "INTERNAL_PART_NUMBER") "MCD-00052")
        (field (name "MANUFACTURER_PART_NUMBER") "RC0402JR-070RL")
        (field (name "PROVIDED_BY") "SUBCO")
      )
      (libsource (lib "MCD_PARTS_database") (part "Resistor"))
    )
    (comp (ref "R41")
      (value "10K")
      (footprint "R0402")
      (description "Resistor,10K,0402,1%,1/16W")
      (fields
        (field (name "INTERNAL_PART_NUMBER") "MCD-00053")
        (field (name "MANUFACTURER_PART_NUMBER") "RC0402FR-0710KL")
        (field (name "PROVIDED_BY") "SUBCO")
      )
      (libsource (lib "MCD_PARTS_database") (part "Resistor"))
    )
    (comp (ref "SB18")
      (value "~")
      (footprint "SOLDER-BRIDGE_R0603-0R")
      (description "Solder Bridge ON")
      (fields
        (field (name "INTERNAL_PART_NUMBER") "MCD-00071")
        (field (name "MANUFACTURER_PART_NUMBER") "RC0603JR-070RL")
        (field (name "PROVIDED_BY") "SUBCO")
      )
      (libsource (lib "") (part "SB_ON_1"))
    )
    (comp (ref "SB20")
      (value "~")
      (footprint "SOLDER-BRIDGE_R0603-0R")
      (description "Solder Bridge ON")
      (fields
        (field (name "INTERNAL_PART_NUMBER") "MCD-00071")
        (field (name "MANUFACTURER_PART_NUMBER") "RC0603JR-070RL")
        (field (name "PROVIDED_BY") "SUBCO")
      )
      (libsource (lib "MCD_PARTS_database") (part "SB_ON"))
    )
    (comp (ref "SB22")
      (value "~")
      (footprint "SOLDER-BRIDGE_R0603-0R")
      (description "Solder Bridge ON")
      (fields
        (field (name "INTERNAL_PART_NUMBER") "MCD-00071")
        (field (name "MANUFACTURER_PART_NUMBER") "RC0603JR-070RL")
        (field (name "PROVIDED_BY") "SUBCO")
      )
      (libsource (lib "MCD_PARTS_database") (part "SB_ON"))
    )
    (comp (ref "SB23")
      (value "~")
      (footprint "SOLDER-BRIDGE_R0603-0R")
      (description "Solder Bridge ON")
      (fields
        (field (name "INTERNAL_PART_NUMBER") "MCD-00071")
        (field (name "MANUFACTURER_PART_NUMBER") "RC0603JR-070RL")
        (field (name "PROVIDED_BY") "SUBCO")
      )
      (libsource (lib "MCD_PARTS_database") (part "SB_ON"))
    )
    (comp (ref "SC1")
      (value "S0951-46R")
      (footprint "CLIP_HARWIN_S0951-46R")
      (description "shield clip Harwin S0951-46R to fix RF shielded cavity")
      (fields
        (field (name "INTERNAL_PART_NUMBER") "MCD-01587")
        (field (name "MANUFACTURER") "HARWIN")
        (field (name "PROVIDED_BY") "SUBCO")
      )
      (libsource (lib "MCD_PARTS_database") (part "Shield-clip_S0951-46R"))
    )
    (comp (ref "SC2")
      (value "S0911-46R")
      (description "shield clip Harwin S0911-46R to fix RF shielded cavity - SMT RFI Shield Clip, Compact (T+R)")
      (fields
        (field (name "INTERNAL_PART_NUMBER") "MCD-02165")
        (field (name "MANUFACTURER") "HARWIN")
        (field (name "PROVIDED_BY") "SUBCO")
      )
      (libsource (lib "MCD_PARTS_database") (part "Shield-clip_S0951-46R"))
    )
    (comp (ref "SC3")
      (value "S0951-46R")
      (footprint "CLIP_HARWIN_S0951-46R")
      (description "shield clip Harwin S0951-46R to fix RF shielded cavity")
      (fields
        (field (name "INTERNAL_PART_NUMBER") "MCD-01587")
        (field (name "MANUFACTURER") "HARWIN")
        (field (name "PROVIDED_BY") "SUBCO")
      )
      (libsource (lib "MCD_PARTS_database") (part "Shield-clip_S0951-46R"))
    )
    (comp (ref "SC4")
      (value "S0951-46R")
      (footprint "CLIP_HARWIN_S0951-46R")
      (description "shield clip Harwin S0951-46R to fix RF shielded cavity")
      (fields
        (field (name "INTERNAL_PART_NUMBER") "MCD-01587")
        (field (name "MANUFACTURER") "HARWIN")
        (field (name "PROVIDED_BY") "SUBCO")
      )
      (libsource (lib "MCD_PARTS_database") (part "Shield-clip_S0951-46R"))
    )
    (comp (ref "SC5")
      (value "S0951-46R")
      (footprint "CLIP_HARWIN_S0951-46R")
      (description "shield clip Harwin S0951-46R to fix RF shielded cavity")
      (fields
        (field (name "INTERNAL_PART_NUMBER") "MCD-01587")
        (field (name "MANUFACTURER") "HARWIN")
        (field (name "PROVIDED_BY") "SUBCO")
      )
      (libsource (lib "MCD_PARTS_database") (part "Shield-clip_S0951-46R"))
    )
    (comp (ref "SC6")
      (value "S0951-46R")
      (footprint "CLIP_HARWIN_S0951-46R")
      (description "shield clip Harwin S0951-46R to fix RF shielded cavity")
      (fields
        (field (name "INTERNAL_PART_NUMBER") "MCD-01587")
        (field (name "MANUFACTURER") "HARWIN")
        (field (name "PROVIDED_BY") "SUBCO")
      )
      (libsource (lib "MCD_PARTS_database") (part "Shield-clip_S0951-46R"))
    )
    (comp (ref "SC7")
      (value "S0951-46R")
      (footprint "CLIP_HARWIN_S0951-46R")
      (description "shield clip Harwin S0951-46R to fix RF shielded cavity")
      (fields
        (field (name "INTERNAL_PART_NUMBER") "MCD-01587")
        (field (name "MANUFACTURER") "HARWIN")
        (field (name "PROVIDED_BY") "SUBCO")
      )
      (libsource (lib "MCD_PARTS_database") (part "Shield-clip_S0951-46R"))
    )
    (comp (ref "SC8")
      (value "S0981-46R")
      (description "shield clip Harwin S0981-46R to fix RF shielded cavity - SMT RFI Shield Clip, Corner (T+R)")
      (fields
        (field (name "INTERNAL_PART_NUMBER") "MCD-02164")
        (field (name "MANUFACTURER") "HARWIN")
        (field (name "PROVIDED_BY") "SUBCO")
      )
      (libsource (lib "MCD_PARTS_database") (part "Shield-clip_S0951-46R"))
    )
    (comp (ref "SC9")
      (value "S0981-46R")
      (description "shield clip Harwin S0981-46R to fix RF shielded cavity - SMT RFI Shield Clip, Corner (T+R)")
      (fields
        (field (name "INTERNAL_PART_NUMBER") "MCD-02164")
        (field (name "MANUFACTURER") "HARWIN")
        (field (name "PROVIDED_BY") "SUBCO")
      )
      (libsource (lib "MCD_PARTS_database") (part "Shield-clip_S0951-46R"))
    )
    (comp (ref "U1")
      (value "BGS13S4N9")
      (footprint "ICC_TSNP-9-3_1P1X1P1_P040")
      (description "Wideband RF SP3T Switch")
      (fields
        (field (name "INTERNAL_PART_NUMBER") "MCD-02018")
        (field (name "MANUFACTURER") "INFINEON")
        (field (name "PROVIDED_BY") "SUBCO")
      )
      (libsource (lib "MCD_PARTS_database") (part "BGS13S4N9"))
    )
    (comp (ref "U3")
      (value "NX3L1T3157GM")
      (footprint "ICC_SOT886_XSON6")
      (description "DC switch - Ultra-Low 0.5ohm  SPDT analog switch")
      (fields
        (field (name "INTERNAL_PART_NUMBER") "MCD-01514")
        (field (name "MANUFACTURER") "NXP")
        (field (name "PROVIDED_BY") "SUBCO")
      )
      (libsource (lib "MCD_PARTS_database") (part "NX3L1T3157GM"))
    )
    (comp (ref "U4")
      (value "NX3L1T3157GM")
      (footprint "ICC_SOT886_XSON6")
      (description "DC switch - Ultra-Low 0.5ohm  SPDT analog switch")
      (fields
        (field (name "INTERNAL_PART_NUMBER") "MCD-01514")
        (field (name "MANUFACTURER") "NXP")
        (field (name "PROVIDED_BY") "SUBCO")
      )
      (libsource (lib "") (part "NX3L1T3157GM_1"))
    )
    (comp (ref "U6")
      (value "STM32WL55JCI7")
      (footprint "ICC_UFBGA73_5X5_P050")
      (description "Multiprotocol Wireless 32-bit MCUwith LPWAN Sub-GHz radio solution")
      (fields
        (field (name "INTERNAL_PART_NUMBER") "MCD-01435")
        (field (name "MANUFACTURER") "STMICROELECTRONICS")
      )
      (libsource (lib "MCD_PARTS_database") (part "STM32WL5x_BGA73"))
    )
    (comp (ref "X3")
      (value "NX2016SA 32MHz")
      (footprint "CRY_NX2016SA_4P")
      (description "Crystal 32MHz, 10pF, +-10 ppm, 50ohm max, SMD")
      (fields
        (field (name "INTERNAL_PART_NUMBER") "MCD-01507")
        (field (name "MANUFACTURER_PART_NUMBER") "NX2016SA 32MHz EXS00A-CS06465")
        (field (name "PROVIDED_BY") "SUBCO")
      )
      (libsource (lib "MCD_PARTS_database") (part "XTAL_4_PINS"))
    )
    (comp (ref "X4")
      (value "32MHz")
      (footprint "CRY_NDK_NT2016SB_4P")
      (description "NT2016SF-32M-END5875A")
      (fields
        (field (name "INTERNAL_PART_NUMBER") "MCD-02240")
        (field (name "MANUFACTURER") "NDK")
        (field (name "MANUFACTURER_PART_NUMBER") "NT2016SF-32M-END5875A")
      )
      (libsource (lib "MCD_PARTS_database") (part "NT2016SB"))
    )
  )
  (nets
    (net (code "1") (name "/FE_CTRL1") (class "Default")
      (node (ref "R27") (pin "1") (pinfunction "1_1") (pintype "passive"))
      (node (ref "U3") (pin "6") (pinfunction "SEL_6") (pintype "passive"))
      (node (ref "U4") (pin "6") (pinfunction "SEL_6") (pintype "passive"))
    )
    (net (code "2") (name "/FE_CTRL2") (class "Default")
      (node (ref "R28") (pin "1") (pinfunction "1_1") (pintype "passive"))
    )
    (net (code "3") (name "/FE_CTRL3") (class "Default")
      (node (ref "SB18") (pin "2") (pinfunction "2_2") (pintype "passive"))
    )
    (net (code "4") (name "/PB0") (class "Default")
      (node (ref "SB20") (pin "1") (pinfunction "1_1") (pintype "passive"))
      (node (ref "U6") (pin "F6") (pinfunction "PB0-VDD_TCXO_F6") (pintype "passive"))
    )
    (net (code "5") (name "/RFI_N") (class "Default")
      (node (ref "C19") (pin "2") (pinfunction "2_2") (pintype "passive"))
      (node (ref "L11") (pin "1") (pinfunction "1_1") (pintype "passive"))
      (node (ref "U6") (pin "H7") (pinfunction "RFI_N_H7") (pintype "passive"))
    )
    (net (code "6") (name "/RFI_P") (class "Default")
      (node (ref "C20") (pin "1") (pinfunction "1_1") (pintype "passive"))
      (node (ref "L11") (pin "2") (pinfunction "2_2") (pintype "passive"))
      (node (ref "U6") (pin "J6") (pinfunction "RFI_P_J6") (pintype "passive"))
    )
    (net (code "7") (name "/XTA") (class "Default")
      (node (ref "C31") (pin "2") (pinfunction "2_2") (pintype "passive"))
      (node (ref "R39") (pin "1") (pinfunction "1_1") (pintype "passive"))
      (node (ref "R41") (pin "2") (pinfunction "2_2") (pintype "passive"))
      (node (ref "U6") (pin "G9") (pinfunction "OSC_IN_G9") (pintype "passive"))
    )
    (net (code "8") (name "GND") (class "Default")
      (node (ref "C11") (pin "1") (pinfunction "1_1") (pintype "passive"))
      (node (ref "C14") (pin "1") (pinfunction "1_1") (pintype "passive"))
      (node (ref "C17") (pin "1") (pinfunction "1_1") (pintype "passive"))
      (node (ref "C19") (pin "1") (pinfunction "1_1") (pintype "passive"))
      (node (ref "C21") (pin "1") (pinfunction "1_1") (pintype "passive"))
      (node (ref "C22") (pin "1") (pinfunction "1_1") (pintype "passive"))
      (node (ref "C24") (pin "2") (pinfunction "2_2") (pintype "passive"))
      (node (ref "C25") (pin "1") (pinfunction "1_1") (pintype "passive"))
      (node (ref "C27") (pin "1") (pinfunction "1_1") (pintype "passive"))
      (node (ref "C30") (pin "1") (pinfunction "1_1") (pintype "passive"))
      (node (ref "C35") (pin "1") (pinfunction "1_1") (pintype "passive"))
      (node (ref "C37") (pin "2") (pinfunction "2_2") (pintype "passive"))
      (node (ref "C38") (pin "1") (pinfunction "1_1") (pintype "passive"))
      (node (ref "C5") (pin "1") (pinfunction "1_1") (pintype "passive"))
      (node (ref "C6") (pin "1") (pinfunction "1_1") (pintype "passive"))
      (node (ref "C7") (pin "1") (pinfunction "1_1") (pintype "passive"))
      (node (ref "C71") (pin "1") (pinfunction "1_1") (pintype "passive"))
      (node (ref "C72") (pin "1") (pinfunction "1_1") (pintype "passive"))
      (node (ref "C73") (pin "1") (pinfunction "1_1") (pintype "passive"))
      (node (ref "C74") (pin "1") (pinfunction "1_1") (pintype "passive"))
      (node (ref "C76") (pin "1") (pinfunction "1_1") (pintype "passive"))
      (node (ref "C77") (pin "2") (pinfunction "2_2") (pintype "passive"))
      (node (ref "C78") (pin "1") (pinfunction "1_1") (pintype "passive"))
      (node (ref "C79") (pin "1") (pinfunction "1_1") (pintype "passive"))
      (node (ref "C8") (pin "1") (pinfunction "1_1") (pintype "passive"))
      (node (ref "C80") (pin "1") (pinfunction "1_1") (pintype "passive"))
      (node (ref "C82") (pin "1") (pinfunction "1_1") (pintype "passive"))
      (node (ref "C85") (pin "1") (pinfunction "1_1") (pintype "passive"))
      (node (ref "C92") (pin "1") (pinfunction "1_1") (pintype "passive"))
      (node (ref "C93") (pin "1") (pinfunction "1_1") (pintype "passive"))
      (node (ref "C97") (pin "1") (pinfunction "1_1") (pintype "passive"))
      (node (ref "CN12") (pin "2") (pinfunction "GND_2") (pintype "passive"))
      (node (ref "CN12") (pin "3") (pinfunction "GND_3") (pintype "passive"))
      (node (ref "CN12") (pin "4") (pinfunction "GND_4") (pintype "passive"))
      (node (ref "CN12") (pin "5") (pinfunction "GND_5") (pintype "passive"))
      (node (ref "CN13") (pin "2") (pinfunction "2_2") (pintype "passive"))
      (node (ref "R41") (pin "1") (pinfunction "1_1") (pintype "passive"))
      (node (ref "SC1") (pin "1") (pinfunction "1_1") (pintype "passive"))
      (node (ref "SC2") (pin "1") (pinfunction "1_1") (pintype "passive"))
      (node (ref "SC3") (pin "1") (pinfunction "1_1") (pintype "passive"))
      (node (ref "SC4") (pin "1") (pinfunction "1_1") (pintype "passive"))
      (node (ref "SC5") (pin "1") (pinfunction "1_1") (pintype "passive"))
      (node (ref "SC6") (pin "1") (pinfunction "1_1") (pintype "passive"))
      (node (ref "SC7") (pin "1") (pinfunction "1_1") (pintype "passive"))
      (node (ref "SC8") (pin "1") (pinfunction "1_1") (pintype "passive"))
      (node (ref "SC9") (pin "1") (pinfunction "1_1") (pintype "passive"))
      (node (ref "U1") (pin "6") (pinfunction "DGND_6") (pintype "passive"))
      (node (ref "U1") (pin "9") (pinfunction "GND_9") (pintype "passive"))
      (node (ref "U3") (pin "2") (pinfunction "GND_2") (pintype "passive"))
      (node (ref "U4") (pin "2") (pinfunction "GND_2") (pintype "passive"))
      (node (ref "U6") (pin "A1") (pinfunction "VSSSMPS_A1") (pintype "passive"))
      (node (ref "U6") (pin "G6") (pinfunction "VSSRF_G6") (pintype "passive"))
      (node (ref "U6") (pin "G7") (pinfunction "VSSRF_G7") (pintype "passive"))
      (node (ref "U6") (pin "G8") (pinfunction "VSSRF_G8") (pintype "passive"))
      (node (ref "U6") (pin "H6") (pinfunction "VSSRF_H6") (pintype "passive"))
      (node (ref "X3") (pin "2") (pinfunction "2_2") (pintype "passive"))
      (node (ref "X3") (pin "4") (pinfunction "4_4") (pintype "passive"))
      (node (ref "X4") (pin "1") (pinfunction "EN_1") (pintype "passive"))
      (node (ref "X4") (pin "2") (pinfunction "GND_2") (pintype "passive"))
    )
    (net (code "9") (name "Net-(C2-Pad1)") (class "Default")
      (node (ref "C2") (pin "1") (pinfunction "1_1") (pintype "passive"))
      (node (ref "C6") (pin "2") (pinfunction "2_2") (pintype "passive"))
      (node (ref "L2") (pin "2") (pinfunction "2_2") (pintype "passive"))
    )
    (net (code "10") (name "Net-(C11-Pad2)") (class "Default")
      (node (ref "C11") (pin "2") (pinfunction "2_2") (pintype "passive"))
      (node (ref "C12") (pin "1") (pinfunction "1_1") (pintype "passive"))
      (node (ref "C15") (pin "2") (pinfunction "2_2") (pintype "passive"))
      (node (ref "L5") (pin "2") (pinfunction "2_2") (pintype "passive"))
    )
    (net (code "11") (name "Net-(C12-Pad2)") (class "Default")
      (node (ref "C12") (pin "2") (pinfunction "2_2") (pintype "passive"))
      (node (ref "L3") (pin "1") (pinfunction "1_1") (pintype "passive"))
    )
    (net (code "12") (name "Net-(C13-Pad1)") (class "Default")
      (node (ref "C13") (pin "1") (pinfunction "1_1") (pintype "passive"))
      (node (ref "L4") (pin "1") (pinfunction "1_1") (pintype "passive"))
    )
    (net (code "13") (name "Net-(C13-Pad2)") (class "Default")
      (node (ref "C13") (pin "2") (pinfunction "2_2") (pintype "passive"))
      (node (ref "C14") (pin "2") (pinfunction "2_2") (pintype "passive"))
      (node (ref "C16") (pin "1") (pinfunction "1_1") (pintype "passive"))
      (node (ref "L6") (pin "2") (pinfunction "2_2") (pintype "passive"))
    )
    (net (code "14") (name "Net-(C15-Pad1)") (class "Default")
      (node (ref "C15") (pin "1") (pinfunction "1_1") (pintype "passive"))
      (node (ref "C22") (pin "2") (pinfunction "2_2") (pintype "passive"))
      (node (ref "L5") (pin "1") (pinfunction "1_1") (pintype "passive"))
      (node (ref "L7") (pin "2") (pinfunction "2_2") (pintype "passive"))
      (node (ref "L9") (pin "2") (pinfunction "2_2") (pintype "passive"))
    )
    (net (code "15") (name "Net-(C16-Pad2)") (class "Default")
      (node (ref "C16") (pin "2") (pinfunction "2_2") (pintype "passive"))
      (node (ref "C21") (pin "2") (pinfunction "2_2") (pintype "passive"))
      (node (ref "L10") (pin "2") (pinfunction "2_2") (pintype "passive"))
      (node (ref "L6") (pin "1") (pinfunction "1_1") (pintype "passive"))
      (node (ref "L8") (pin "2") (pinfunction "2_2") (pintype "passive"))
    )
    (net (code "16") (name "Net-(C30-Pad2)") (class "Default")
      (node (ref "C30") (pin "2") (pinfunction "2_2") (pintype "passive"))
      (node (ref "R39") (pin "2") (pinfunction "2_2") (pintype "passive"))
      (node (ref "X3") (pin "1") (pinfunction "1_1") (pintype "passive"))
    )
    (net (code "17") (name "Net-(C31-Pad1)") (class "Default")
      (node (ref "C31") (pin "1") (pinfunction "1_1") (pintype "passive"))
      (node (ref "R2") (pin "2") (pinfunction "2_2") (pintype "passive"))
    )
    (net (code "18") (name "Net-(C38-Pad2)") (class "Default")
      (node (ref "C38") (pin "2") (pinfunction "2_2") (pintype "passive"))
      (node (ref "R40") (pin "2") (pinfunction "2_2") (pintype "passive"))
      (node (ref "X3") (pin "3") (pinfunction "3_3") (pintype "passive"))
    )
    (net (code "19") (name "Net-(CN12-RF)") (class "Default")
      (node (ref "C5") (pin "2") (pinfunction "2_2") (pintype "passive"))
      (node (ref "CN12") (pin "1") (pinfunction "RF_1") (pintype "passive"))
      (node (ref "L2") (pin "1") (pinfunction "1_1") (pintype "passive"))
    )
    (net (code "20") (name "Net-(CN13-Pad1)") (class "Default")
      (node (ref "CN13") (pin "1") (pinfunction "1_1") (pintype "passive"))
      (node (ref "R33") (pin "1") (pinfunction "1_1") (pintype "passive"))
    )
    (net (code "21") (name "Net-(L13-Pad2)") (class "Default")
      (node (ref "L13") (pin "2") (pinfunction "2_2") (pintype "passive"))
      (node (ref "R32") (pin "2") (pinfunction "2_2") (pintype "passive"))
      (node (ref "R33") (pin "2") (pinfunction "2_2") (pintype "passive"))
    )
    (net (code "22") (name "Net-(R29-Pad2)") (class "Default")
      (node (ref "R29") (pin "2") (pinfunction "2_2") (pintype "passive"))
      (node (ref "SB18") (pin "1") (pinfunction "1_1") (pintype "passive"))
    )
    (net (code "23") (name "Net-(U1-RF1)") (class "Default")
      (node (ref "C17") (pin "2") (pinfunction "2_2") (pintype "passive"))
      (node (ref "C20") (pin "2") (pinfunction "2_2") (pintype "passive"))
      (node (ref "U1") (pin "3") (pinfunction "RF1_3") (pintype "passive"))
    )
    (net (code "24") (name "Net-(U1-RF2)") (class "Default")
      (node (ref "C7") (pin "2") (pinfunction "2_2") (pintype "passive"))
      (node (ref "L3") (pin "2") (pinfunction "2_2") (pintype "passive"))
      (node (ref "U1") (pin "5") (pinfunction "RF2_5") (pintype "passive"))
    )
    (net (code "25") (name "Net-(U1-RF3)") (class "Default")
      (node (ref "C8") (pin "2") (pinfunction "2_2") (pintype "passive"))
      (node (ref "L4") (pin "2") (pinfunction "2_2") (pintype "passive"))
      (node (ref "U1") (pin "2") (pinfunction "RF3_2") (pintype "passive"))
    )
    (net (code "26") (name "Net-(U1-RFin)") (class "Default")
      (node (ref "C2") (pin "2") (pinfunction "2_2") (pintype "passive"))
      (node (ref "U1") (pin "4") (pinfunction "RFin_4") (pintype "passive"))
    )
    (net (code "27") (name "Net-(U1-V1)") (class "Default")
      (node (ref "C72") (pin "2") (pinfunction "2_2") (pintype "passive"))
      (node (ref "R27") (pin "2") (pinfunction "2_2") (pintype "passive"))
      (node (ref "U1") (pin "1") (pinfunction "V1_1") (pintype "passive"))
    )
    (net (code "28") (name "Net-(U1-V2)") (class "Default")
      (node (ref "C71") (pin "2") (pinfunction "2_2") (pintype "passive"))
      (node (ref "R28") (pin "2") (pinfunction "2_2") (pintype "passive"))
      (node (ref "U1") (pin "8") (pinfunction "V2_8") (pintype "passive"))
    )
    (net (code "29") (name "Net-(U1-VDD)") (class "Default")
      (node (ref "C73") (pin "2") (pinfunction "2_2") (pintype "passive"))
      (node (ref "R29") (pin "1") (pinfunction "1_1") (pintype "passive"))
      (node (ref "U1") (pin "7") (pinfunction "VDD_7") (pintype "passive"))
    )
    (net (code "30") (name "Net-(U3-Y0)") (class "Default")
      (node (ref "R37") (pin "1") (pinfunction "1_1") (pintype "passive"))
      (node (ref "U3") (pin "3") (pinfunction "Y0_3") (pintype "passive"))
    )
    (net (code "31") (name "Net-(U3-Y1)") (class "Default")
      (node (ref "R38") (pin "1") (pinfunction "1_1") (pintype "passive"))
      (node (ref "U3") (pin "1") (pinfunction "Y1_1") (pintype "passive"))
    )
    (net (code "32") (name "Net-(U4-Y0)") (class "Default")
      (node (ref "C24") (pin "1") (pinfunction "1_1") (pintype "passive"))
      (node (ref "L7") (pin "1") (pinfunction "1_1") (pintype "passive"))
      (node (ref "U4") (pin "3") (pinfunction "Y0_3") (pintype "passive"))
    )
    (net (code "33") (name "Net-(U4-Y1)") (class "Default")
      (node (ref "C25") (pin "2") (pinfunction "2_2") (pintype "passive"))
      (node (ref "L8") (pin "1") (pinfunction "1_1") (pintype "passive"))
      (node (ref "U4") (pin "1") (pinfunction "Y1_1") (pintype "passive"))
    )
    (net (code "34") (name "Net-(U4-Z)") (class "Default")
      (node (ref "C74") (pin "2") (pinfunction "2_2") (pintype "passive"))
      (node (ref "C76") (pin "2") (pinfunction "2_2") (pintype "passive"))
      (node (ref "C92") (pin "2") (pinfunction "2_2") (pintype "passive"))
      (node (ref "U4") (pin "4") (pinfunction "Z_4") (pintype "passive"))
      (node (ref "U6") (pin "H9") (pinfunction "VR_PA_H9") (pintype "passive"))
    )
    (net (code "35") (name "Net-(U6A-OSC_OUT)") (class "Default")
      (node (ref "R40") (pin "1") (pinfunction "1_1") (pintype "passive"))
      (node (ref "U6") (pin "F8") (pinfunction "OSC_OUT_F8") (pintype "passive"))
    )
    (net (code "36") (name "Net-(U6A-RFO_HP)") (class "Default")
      (node (ref "L9") (pin "1") (pinfunction "1_1") (pintype "passive"))
      (node (ref "U6") (pin "J9") (pinfunction "RFO_HP_J9") (pintype "passive"))
    )
    (net (code "37") (name "Net-(U6A-RFO_LP)") (class "Default")
      (node (ref "L10") (pin "1") (pinfunction "1_1") (pintype "passive"))
      (node (ref "U6") (pin "J8") (pinfunction "RFO_LP_J8") (pintype "passive"))
    )
    (net (code "38") (name "Net-(U6B-VFBSMPS)") (class "Default")
      (node (ref "C85") (pin "2") (pinfunction "2_2") (pintype "passive"))
      (node (ref "L13") (pin "1") (pinfunction "1_1") (pintype "passive"))
      (node (ref "SB22") (pin "2") (pinfunction "2_2") (pintype "passive"))
      (node (ref "U6") (pin "B2") (pinfunction "VFBSMPS_B2") (pintype "passive"))
    )
    (net (code "39") (name "Net-(U6B-VLXSMPS)") (class "Default")
      (node (ref "R32") (pin "1") (pinfunction "1_1") (pintype "passive"))
      (node (ref "U6") (pin "B1") (pinfunction "VLXSMPS_B1") (pintype "passive"))
    )
    (net (code "40") (name "Net-(X4-OUT)") (class "Default")
      (node (ref "R2") (pin "1") (pinfunction "1_1") (pintype "passive"))
      (node (ref "X4") (pin "3") (pinfunction "OUT_3") (pintype "passive"))
    )
    (net (code "41") (name "Net-(X4-VDD)") (class "Default")
      (node (ref "C27") (pin "2") (pinfunction "2_2") (pintype "passive"))
      (node (ref "L12") (pin "1") (pinfunction "1_1") (pintype "passive"))
      (node (ref "X4") (pin "4") (pinfunction "VDD_4") (pintype "passive"))
    )
    (net (code "42") (name "PB0_VDD_TCXO") (class "Default")
      (node (ref "C77") (pin "1") (pinfunction "1_1") (pintype "passive"))
      (node (ref "C79") (pin "2") (pinfunction "2_2") (pintype "passive"))
      (node (ref "C97") (pin "2") (pinfunction "2_2") (pintype "passive"))
      (node (ref "L12") (pin "2") (pinfunction "2_2") (pintype "passive"))
      (node (ref "SB20") (pin "2") (pinfunction "2_2") (pintype "passive"))
    )
    (net (code "43") (name "VDDPA") (class "Default")
      (node (ref "C78") (pin "2") (pinfunction "2_2") (pintype "passive"))
      (node (ref "U3") (pin "4") (pinfunction "Z_4") (pintype "passive"))
      (node (ref "U6") (pin "H8") (pinfunction "VDDPA_H8") (pintype "passive"))
    )
    (net (code "44") (name "VDDRF") (class "Default")
      (node (ref "C82") (pin "2") (pinfunction "2_2") (pintype "passive"))
      (node (ref "C93") (pin "2") (pinfunction "2_2") (pintype "passive"))
      (node (ref "R37") (pin "2") (pinfunction "2_2") (pintype "passive"))
      (node (ref "SB23") (pin "1") (pinfunction "1_1") (pintype "passive"))
      (node (ref "U6") (pin "E8") (pinfunction "VDDRF_E8") (pintype "passive"))
    )
    (net (code "45") (name "VDDRF1V55") (class "Default")
      (node (ref "C80") (pin "2") (pinfunction "2_2") (pintype "passive"))
      (node (ref "R38") (pin "2") (pinfunction "2_2") (pintype "passive"))
      (node (ref "SB22") (pin "1") (pinfunction "1_1") (pintype "passive"))
      (node (ref "U6") (pin "F7") (pinfunction "VDDRF1V55_F7") (pintype "passive"))
    )
    (net (code "46") (name "VDD_APP") (class "Default")
      (node (ref "U3") (pin "5") (pinfunction "VCC_5") (pintype "passive"))
      (node (ref "U4") (pin "5") (pinfunction "VCC_5") (pintype "passive"))
    )
    (net (code "47") (name "VDD_RF") (class "Default")
      (node (ref "C35") (pin "2") (pinfunction "2_2") (pintype "passive"))
      (node (ref "C37") (pin "1") (pinfunction "1_1") (pintype "passive"))
      (node (ref "SB23") (pin "2") (pinfunction "2_2") (pintype "passive"))
      (node (ref "U6") (pin "A2") (pinfunction "VDDSMPS_A2") (pintype "passive"))
    )
  )
)
